# lp_relay.net
KiCad netlist of a schematic drawn in EAGLE
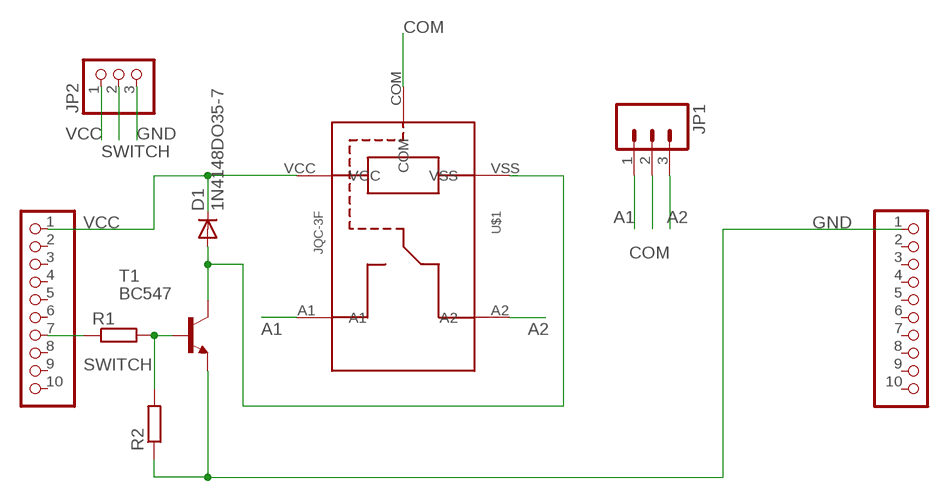
[diagram p0: schematic, sheet 1]

(export (version "E")
  (design (tool "Eeschema 10.0.6"))
  (components
    (comp (ref "D1")
      (value "1N4148DO35-7")
      (footprint "eagle-import:DO35-7")
      (libsource (lib "eagle-import") (part "1N4148DO35-7"))
    )
    (comp (ref "J1")
      (value "J1")
      (footprint "eagle-import:1X10")
      (libsource (lib "eagle-import") (part "PINHD-1X10"))
    )
    (comp (ref "J2")
      (value "J2")
      (footprint "eagle-import:1X10")
      (libsource (lib "eagle-import") (part "PINHD-1X10"))
    )
    (comp (ref "JP1")
      (value "M03-SCREW-5MM")
      (footprint "eagle-import:SCREWTERMINAL-5MM-3")
      (libsource (lib "eagle-import") (part "M03-SCREW-5MM"))
    )
    (comp (ref "JP2")
      (value "PINHD-1X3")
      (footprint "eagle-import:1X03")
      (libsource (lib "eagle-import") (part "PINHD-1X3"))
    )
    (comp (ref "R1")
      (value "R-EU_0207/10")
      (footprint "eagle-import:0207_10")
      (libsource (lib "eagle-import") (part "R-EU_0207/10"))
    )
    (comp (ref "R2")
      (value "R-EU_0207/10")
      (footprint "eagle-import:0207_10")
      (libsource (lib "eagle-import") (part "R-EU_0207/10"))
    )
    (comp (ref "T1")
      (value "BC547")
      (footprint "eagle-import:TO92")
      (libsource (lib "eagle-import") (part "BC547"))
    )
    (comp (ref "U$1")
      (value "JQC-3F")
      (footprint "eagle-import:JQC-3F")
      (libsource (lib "eagle-import") (part "JQC-3F"))
    )
  )
  (nets
    (net (code "1") (name "/A1") (class "Default")
      (node (ref "JP1") (pin "1") (pinfunction "1_1") (pintype "passive"))
      (node (ref "U$1") (pin "A1") (pinfunction "A1_A1") (pintype "bidirectional"))
    )
    (net (code "2") (name "/A2") (class "Default")
      (node (ref "JP1") (pin "3") (pinfunction "3_3") (pintype "passive"))
      (node (ref "U$1") (pin "A2") (pinfunction "A2_A2") (pintype "bidirectional"))
    )
    (net (code "3") (name "/COM") (class "Default")
      (node (ref "JP1") (pin "2") (pinfunction "2_2") (pintype "passive"))
      (node (ref "U$1") (pin "COM") (pinfunction "COM_COM") (pintype "bidirectional"))
    )
    (net (code "4") (name "/GND") (class "Default")
      (node (ref "J2") (pin "1") (pinfunction "1_1") (pintype "passive"))
      (node (ref "JP2") (pin "3") (pinfunction "3_3") (pintype "passive"))
      (node (ref "R2") (pin "1") (pinfunction "1_1") (pintype "passive"))
      (node (ref "T1") (pin "1") (pinfunction "E_1") (pintype "passive"))
    )
    (net (code "5") (name "/SWITCH") (class "Default")
      (node (ref "J1") (pin "7") (pinfunction "7_7") (pintype "passive"))
      (node (ref "JP2") (pin "2") (pinfunction "2_2") (pintype "passive"))
      (node (ref "R1") (pin "1") (pinfunction "1_1") (pintype "passive"))
    )
    (net (code "6") (name "/VCC") (class "Default")
      (node (ref "D1") (pin "C") (pinfunction "C_C") (pintype "passive"))
      (node (ref "J1") (pin "1") (pinfunction "1_1") (pintype "passive"))
      (node (ref "JP2") (pin "1") (pinfunction "1_1") (pintype "passive"))
      (node (ref "U$1") (pin "VCC") (pinfunction "VCC_VCC") (pintype "power_in"))
    )
    (net (code "7") (name "Net-(T1-B)") (class "Default")
      (node (ref "R1") (pin "2") (pinfunction "2_2") (pintype "passive"))
      (node (ref "R2") (pin "2") (pinfunction "2_2") (pintype "passive"))
      (node (ref "T1") (pin "2") (pinfunction "B_2") (pintype "passive"))
    )
    (net (code "8") (name "Net-(T1-C)") (class "Default")
      (node (ref "D1") (pin "A") (pinfunction "A_A") (pintype "passive"))
      (node (ref "T1") (pin "3") (pinfunction "C_3") (pintype "passive"))
      (node (ref "U$1") (pin "VSS") (pinfunction "VSS_VSS") (pintype "power_in"))
    )
    (net (code "9") (name "unconnected-(J1-Pad2)") (class "Default")
      (node (ref "J1") (pin "2") (pinfunction "2_2") (pintype "passive"))
    )
    (net (code "10") (name "unconnected-(J1-Pad3)") (class "Default")
      (node (ref "J1") (pin "3") (pinfunction "3_3") (pintype "passive"))
    )
    (net (code "11") (name "unconnected-(J1-Pad4)") (class "Default")
      (node (ref "J1") (pin "4") (pinfunction "4_4") (pintype "passive"))
    )
    (net (code "12") (name "unconnected-(J1-Pad5)") (class "Default")
      (node (ref "J1") (pin "5") (pinfunction "5_5") (pintype "passive"))
    )
    (net (code "13") (name "unconnected-(J1-Pad6)") (class "Default")
      (node (ref "J1") (pin "6") (pinfunction "6_6") (pintype "passive"))
    )
    (net (code "14") (name "unconnected-(J1-Pad8)") (class "Default")
      (node (ref "J1") (pin "8") (pinfunction "8_8") (pintype "passive"))
    )
    (net (code "15") (name "unconnected-(J1-Pad9)") (class "Default")
      (node (ref "J1") (pin "9") (pinfunction "9_9") (pintype "passive"))
    )
    (net (code "16") (name "unconnected-(J1-Pad10)") (class "Default")
      (node (ref "J1") (pin "10") (pinfunction "10_10") (pintype "passive"))
    )
    (net (code "17") (name "unconnected-(J2-Pad2)") (class "Default")
      (node (ref "J2") (pin "2") (pinfunction "2_2") (pintype "passive"))
    )
    (net (code "18") (name "unconnected-(J2-Pad3)") (class "Default")
      (node (ref "J2") (pin "3") (pinfunction "3_3") (pintype "passive"))
    )
    (net (code "19") (name "unconnected-(J2-Pad4)") (class "Default")
      (node (ref "J2") (pin "4") (pinfunction "4_4") (pintype "passive"))
    )
    (net (code "20") (name "unconnected-(J2-Pad5)") (class "Default")
      (node (ref "J2") (pin "5") (pinfunction "5_5") (pintype "passive"))
    )
    (net (code "21") (name "unconnected-(J2-Pad6)") (class "Default")
      (node (ref "J2") (pin "6") (pinfunction "6_6") (pintype "passive"))
    )
    (net (code "22") (name "unconnected-(J2-Pad7)") (class "Default")
      (node (ref "J2") (pin "7") (pinfunction "7_7") (pintype "passive"))
    )
    (net (code "23") (name "unconnected-(J2-Pad8)") (class "Default")
      (node (ref "J2") (pin "8") (pinfunction "8_8") (pintype "passive"))
    )
    (net (code "24") (name "unconnected-(J2-Pad9)") (class "Default")
      (node (ref "J2") (pin "9") (pinfunction "9_9") (pintype "passive"))
    )
    (net (code "25") (name "unconnected-(J2-Pad10)") (class "Default")
      (node (ref "J2") (pin "10") (pinfunction "10_10") (pintype "passive"))
    )
  )
)
